# Main_Board_v6.net
KiCad netlist of a schematic drawn in EAGLE
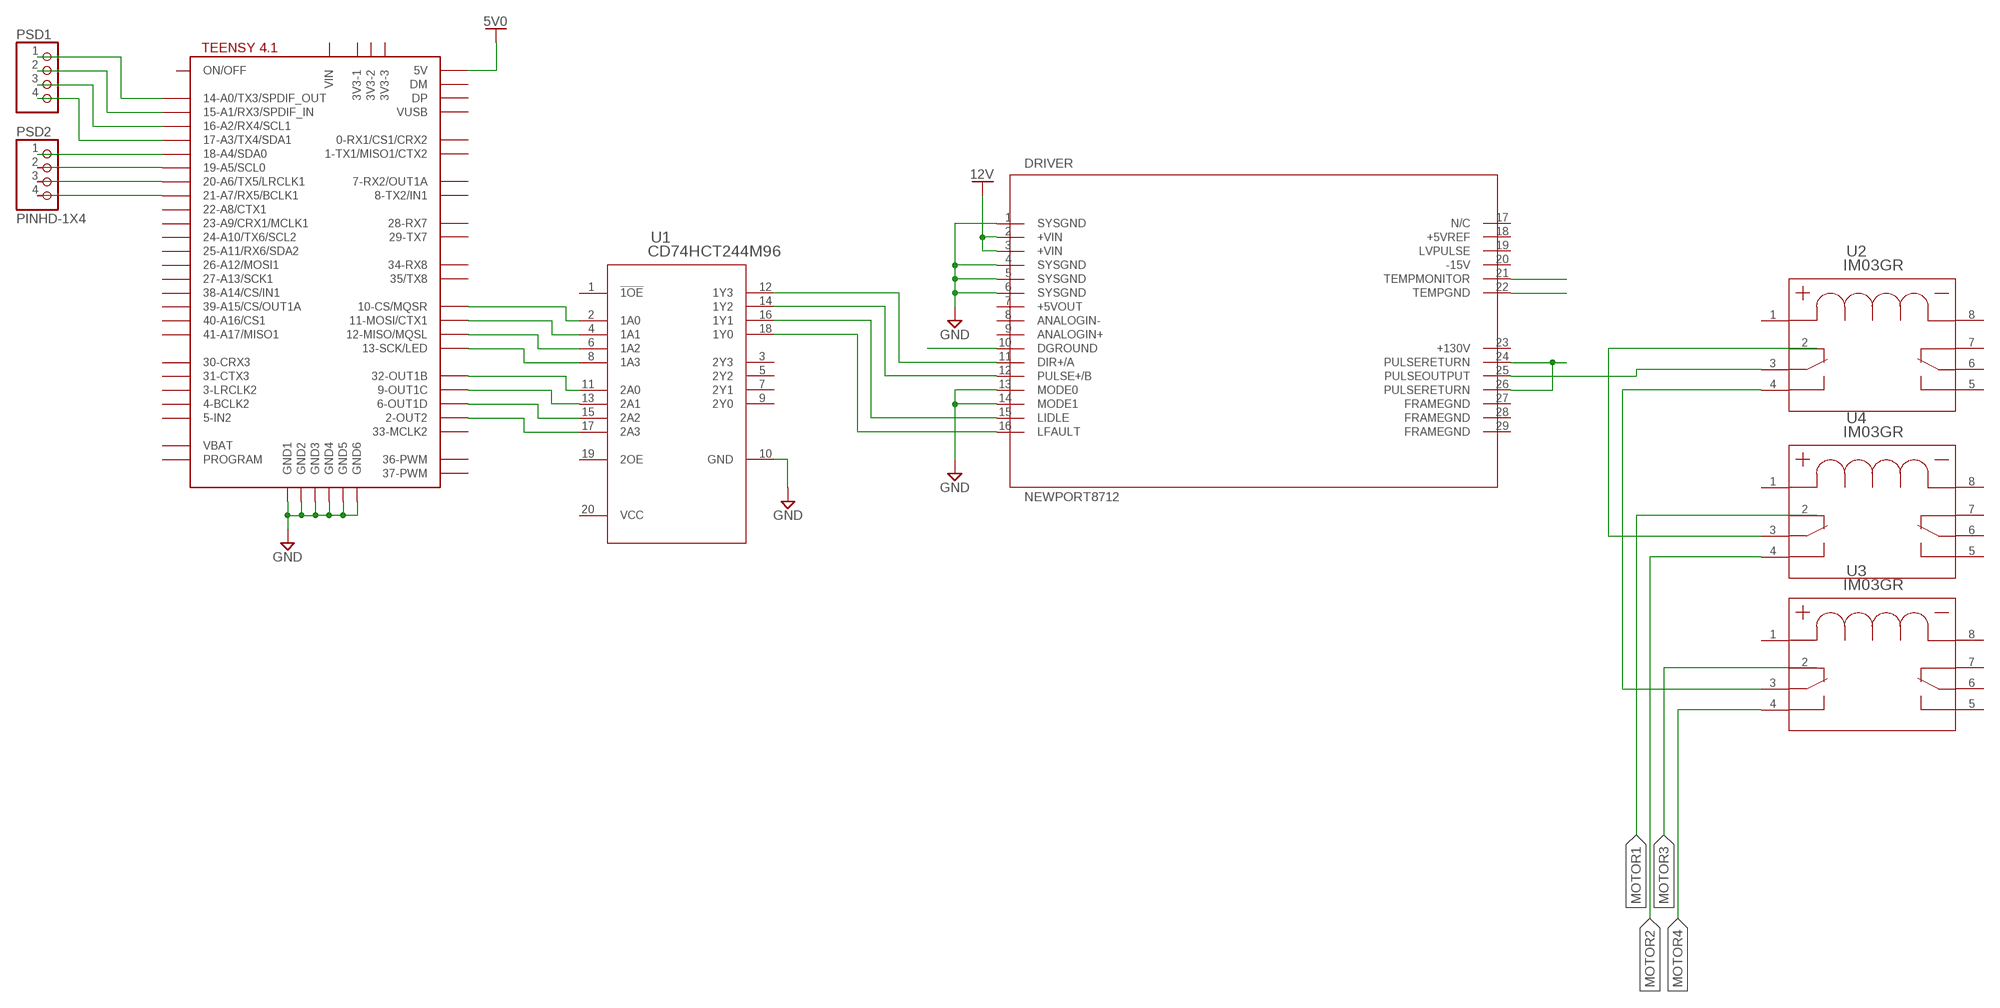
[diagram p0: schematic, sheet 1]

(export (version "E")
  (design (tool "Eeschema 10.0.6"))
  (components
    (comp (ref "DRIVER")
      (value "NEWPORT8712")
      (footprint "eagle-import:NEWPORT8712")
      (libsource (lib "eagle-import") (part "NEWPORT8712"))
    )
    (comp (ref "PSD1")
      (value "PINHD-1X4")
      (footprint "eagle-import:1X04")
      (libsource (lib "eagle-import") (part "PINHD-1X4"))
    )
    (comp (ref "PSD2")
      (value "PINHD-1X4")
      (footprint "eagle-import:1X04")
      (libsource (lib "eagle-import") (part "PINHD-1X4"))
    )
    (comp (ref "U$2")
      (value "TEENSY41-E")
      (footprint "eagle-import:TENNSY41-E")
      (libsource (lib "eagle-import") (part "TEENSY41-E"))
    )
    (comp (ref "U1")
      (value "CD74HCT244M96")
      (footprint "eagle-import:DW20")
      (fields
        (field (name "GENERIC_PART_NUMBER") "CD74HCT244")
        (field (name "MANUFACTURER") "Texas Instruments")
      )
      (libsource (lib "eagle-import") (part "CD74HCT244M96"))
    )
    (comp (ref "U2")
      (value "IM03GR")
      (footprint "eagle-import:RELAY8-239X396_230")
      (fields (field (name "COPYRIGHT") "Copyright (C) 2016 Accelerated Designs. All rights reserved"))
      (libsource (lib "eagle-import") (part "IM03GR"))
    )
    (comp (ref "U3")
      (value "IM03GR")
      (footprint "eagle-import:RELAY8-239X396_230")
      (fields (field (name "COPYRIGHT") "Copyright (C) 2016 Accelerated Designs. All rights reserved"))
      (libsource (lib "eagle-import") (part "IM03GR"))
    )
    (comp (ref "U4")
      (value "IM03GR")
      (footprint "eagle-import:RELAY8-239X396_230")
      (fields (field (name "COPYRIGHT") "Copyright (C) 2016 Accelerated Designs. All rights reserved"))
      (libsource (lib "eagle-import") (part "IM03GR"))
    )
  )
  (nets
    (net (code "1") (name "/VCC") (class "Default")
      (node (ref "U1") (pin "20") (pinfunction "VCC_20") (pintype "power_in"))
    )
    (net (code "2") (name "5V0") (class "Default")
      (node (ref "U$2") (pin "+5V") (pinfunction "5V_+5V") (pintype "bidirectional"))
    )
    (net (code "3") (name "12V") (class "Default")
      (node (ref "DRIVER") (pin "2") (pinfunction "+VIN_2") (pintype "bidirectional"))
      (node (ref "DRIVER") (pin "3") (pinfunction "+VIN_3") (pintype "bidirectional"))
    )
    (net (code "4") (name "GND") (class "Default")
      (node (ref "DRIVER") (pin "1") (pinfunction "SYSGND_1") (pintype "bidirectional"))
      (node (ref "DRIVER") (pin "13") (pinfunction "MODE0_13") (pintype "bidirectional"))
      (node (ref "DRIVER") (pin "14") (pinfunction "MODE1_14") (pintype "bidirectional"))
      (node (ref "DRIVER") (pin "4") (pinfunction "SYSGND_4") (pintype "bidirectional"))
      (node (ref "DRIVER") (pin "5") (pinfunction "SYSGND_5") (pintype "bidirectional"))
      (node (ref "DRIVER") (pin "6") (pinfunction "SYSGND_6") (pintype "bidirectional"))
      (node (ref "U$2") (pin "GND1") (pinfunction "GND1_GND1") (pintype "bidirectional"))
      (node (ref "U$2") (pin "GND2") (pinfunction "GND2_GND2") (pintype "bidirectional"))
      (node (ref "U$2") (pin "GND3") (pinfunction "GND3_GND3") (pintype "bidirectional"))
      (node (ref "U$2") (pin "GND4") (pinfunction "GND4_GND4") (pintype "bidirectional"))
      (node (ref "U$2") (pin "GND5") (pinfunction "GND5_GND5") (pintype "bidirectional"))
      (node (ref "U$2") (pin "GND6") (pinfunction "GND6_GND6") (pintype "bidirectional"))
      (node (ref "U1") (pin "10") (pinfunction "GND_10") (pintype "power_in"))
    )
    (net (code "5") (name "MOTOR1") (class "Default")
      (node (ref "U4") (pin "2") (pinfunction "2_2") (pintype "passive"))
    )
    (net (code "6") (name "MOTOR2") (class "Default")
      (node (ref "U4") (pin "4") (pinfunction "4_4") (pintype "passive"))
    )
    (net (code "7") (name "MOTOR3") (class "Default")
      (node (ref "U3") (pin "2") (pinfunction "2_2") (pintype "passive"))
    )
    (net (code "8") (name "MOTOR4") (class "Default")
      (node (ref "U3") (pin "4") (pinfunction "4_4") (pintype "passive"))
    )
    (net (code "9") (name "Net-(DRIVER-DIR+{slash}A)") (class "Default")
      (node (ref "DRIVER") (pin "11") (pinfunction "DIR+/A_11") (pintype "bidirectional"))
      (node (ref "U1") (pin "12") (pinfunction "1Y3_12") (pintype "output"))
    )
    (net (code "10") (name "Net-(DRIVER-LFAULT)") (class "Default")
      (node (ref "DRIVER") (pin "16") (pinfunction "LFAULT_16") (pintype "bidirectional"))
      (node (ref "U1") (pin "18") (pinfunction "1Y0_18") (pintype "output"))
    )
    (net (code "11") (name "Net-(DRIVER-LIDLE)") (class "Default")
      (node (ref "DRIVER") (pin "15") (pinfunction "LIDLE_15") (pintype "bidirectional"))
      (node (ref "U1") (pin "16") (pinfunction "1Y1_16") (pintype "output"))
    )
    (net (code "12") (name "Net-(DRIVER-PULSE+{slash}B)") (class "Default")
      (node (ref "DRIVER") (pin "12") (pinfunction "PULSE+/B_12") (pintype "bidirectional"))
      (node (ref "U1") (pin "14") (pinfunction "1Y2_14") (pintype "output"))
    )
    (net (code "13") (name "Net-(DRIVER-PULSEOUTPUT)") (class "Default")
      (node (ref "DRIVER") (pin "25") (pinfunction "PULSEOUTPUT_25") (pintype "bidirectional"))
      (node (ref "U2") (pin "3") (pinfunction "3_3") (pintype "passive"))
    )
    (net (code "14") (name "Net-(DRIVER-PULSERETURN-Pad24)") (class "Default")
      (node (ref "DRIVER") (pin "24") (pinfunction "PULSERETURN_24") (pintype "bidirectional"))
      (node (ref "DRIVER") (pin "26") (pinfunction "PULSERETURN_26") (pintype "bidirectional"))
    )
    (net (code "15") (name "Net-(PSD1-Pad1)") (class "Default")
      (node (ref "PSD1") (pin "1") (pinfunction "1_1") (pintype "passive"))
      (node (ref "U$2") (pin "14-A0/TX3/SPDIF_OUT") (pinfunction "14-A0/TX3/SPDIF_OUT_14-A0/TX3/SPDIF_OUT") (pintype "bidirectional"))
    )
    (net (code "16") (name "Net-(PSD1-Pad2)") (class "Default")
      (node (ref "PSD1") (pin "2") (pinfunction "2_2") (pintype "passive"))
      (node (ref "U$2") (pin "15-A1/RX3/SPDIF_IN") (pinfunction "15-A1/RX3/SPDIF_IN_15-A1/RX3/SPDIF_IN") (pintype "bidirectional"))
    )
    (net (code "17") (name "Net-(PSD1-Pad3)") (class "Default")
      (node (ref "PSD1") (pin "3") (pinfunction "3_3") (pintype "passive"))
      (node (ref "U$2") (pin "16-A2/RX4/SCL1") (pinfunction "16-A2/RX4/SCL1_16-A2/RX4/SCL1") (pintype "bidirectional"))
    )
    (net (code "18") (name "Net-(PSD1-Pad4)") (class "Default")
      (node (ref "PSD1") (pin "4") (pinfunction "4_4") (pintype "passive"))
      (node (ref "U$2") (pin "17-A3/TX4/SDA1") (pinfunction "17-A3/TX4/SDA1_17-A3/TX4/SDA1") (pintype "bidirectional"))
    )
    (net (code "19") (name "Net-(PSD2-Pad1)") (class "Default")
      (node (ref "PSD2") (pin "1") (pinfunction "1_1") (pintype "passive"))
      (node (ref "U$2") (pin "18-A4/SDA0") (pinfunction "18-A4/SDA0_18-A4/SDA0") (pintype "bidirectional"))
    )
    (net (code "20") (name "Net-(PSD2-Pad2)") (class "Default")
      (node (ref "PSD2") (pin "2") (pinfunction "2_2") (pintype "passive"))
      (node (ref "U$2") (pin "19-A5/SCL0") (pinfunction "19-A5/SCL0_19-A5/SCL0") (pintype "bidirectional"))
    )
    (net (code "21") (name "Net-(PSD2-Pad3)") (class "Default")
      (node (ref "PSD2") (pin "3") (pinfunction "3_3") (pintype "passive"))
      (node (ref "U$2") (pin "20-A6/TX5/LRCLK1") (pinfunction "20-A6/TX5/LRCLK1_20-A6/TX5/LRCLK1") (pintype "bidirectional"))
    )
    (net (code "22") (name "Net-(PSD2-Pad4)") (class "Default")
      (node (ref "PSD2") (pin "4") (pinfunction "4_4") (pintype "passive"))
      (node (ref "U$2") (pin "21-A7/RX5/BCLK1") (pinfunction "21-A7/RX5/BCLK1_21-A7/RX5/BCLK1") (pintype "bidirectional"))
    )
    (net (code "23") (name "Net-(U$2-10-CS{slash}MQSR)") (class "Default")
      (node (ref "U$2") (pin "10-CS\\MQSR") (pinfunction "10-CS/MQSR_10-CS\\MQSR") (pintype "bidirectional"))
      (node (ref "U1") (pin "2") (pinfunction "1A0_2") (pintype "input"))
    )
    (net (code "24") (name "Net-(U1-1A1)") (class "Default")
      (node (ref "U$2") (pin "11-MOSI/CTX1") (pinfunction "11-MOSI/CTX1_11-MOSI/CTX1") (pintype "bidirectional"))
      (node (ref "U1") (pin "4") (pinfunction "1A1_4") (pintype "input"))
    )
    (net (code "25") (name "Net-(U1-1A2)") (class "Default")
      (node (ref "U$2") (pin "12-MISO/MQSL") (pinfunction "12-MISO/MQSL_12-MISO/MQSL") (pintype "bidirectional"))
      (node (ref "U1") (pin "6") (pinfunction "1A2_6") (pintype "input"))
    )
    (net (code "26") (name "Net-(U1-1A3)") (class "Default")
      (node (ref "U$2") (pin "13-SCK/LED") (pinfunction "13-SCK/LED_13-SCK/LED") (pintype "bidirectional"))
      (node (ref "U1") (pin "8") (pinfunction "1A3_8") (pintype "input"))
    )
    (net (code "27") (name "Net-(U1-2A0)") (class "Default")
      (node (ref "U$2") (pin "32-OUT1B") (pinfunction "32-OUT1B_32-OUT1B") (pintype "bidirectional"))
      (node (ref "U1") (pin "11") (pinfunction "2A0_11") (pintype "input"))
    )
    (net (code "28") (name "Net-(U1-2A1)") (class "Default")
      (node (ref "U$2") (pin "9-OUT1C") (pinfunction "9-OUT1C_9-OUT1C") (pintype "bidirectional"))
      (node (ref "U1") (pin "13") (pinfunction "2A1_13") (pintype "input"))
    )
    (net (code "29") (name "Net-(U1-2A2)") (class "Default")
      (node (ref "U$2") (pin "6-OUT1D") (pinfunction "6-OUT1D_6-OUT1D") (pintype "bidirectional"))
      (node (ref "U1") (pin "15") (pinfunction "2A2_15") (pintype "input"))
    )
    (net (code "30") (name "Net-(U1-2A3)") (class "Default")
      (node (ref "U$2") (pin "2-OUT2") (pinfunction "2-OUT2_2-OUT2") (pintype "bidirectional"))
      (node (ref "U1") (pin "17") (pinfunction "2A3_17") (pintype "input"))
    )
    (net (code "31") (name "Net-(U2-Pad2)") (class "Default")
      (node (ref "U2") (pin "2") (pinfunction "2_2") (pintype "passive"))
      (node (ref "U4") (pin "3") (pinfunction "3_3") (pintype "passive"))
    )
    (net (code "32") (name "Net-(U2-Pad4)") (class "Default")
      (node (ref "U2") (pin "4") (pinfunction "4_4") (pintype "passive"))
      (node (ref "U3") (pin "3") (pinfunction "3_3") (pintype "passive"))
    )
    (net (code "33") (name "unconnected-(DRIVER-+5VOUT-Pad7)") (class "Default")
      (node (ref "DRIVER") (pin "7") (pinfunction "+5VOUT_7") (pintype "bidirectional"))
    )
    (net (code "34") (name "unconnected-(DRIVER-+5VREF-Pad18)") (class "Default")
      (node (ref "DRIVER") (pin "18") (pinfunction "+5VREF_18") (pintype "bidirectional"))
    )
    (net (code "35") (name "unconnected-(DRIVER-+130V-Pad23)") (class "Default")
      (node (ref "DRIVER") (pin "23") (pinfunction "+130V_23") (pintype "bidirectional"))
    )
    (net (code "36") (name "unconnected-(DRIVER--15V-Pad20)") (class "Default")
      (node (ref "DRIVER") (pin "20") (pinfunction "-15V_20") (pintype "bidirectional"))
    )
    (net (code "37") (name "unconnected-(DRIVER-ANALOGIN+-Pad9)") (class "Default")
      (node (ref "DRIVER") (pin "9") (pinfunction "ANALOGIN+_9") (pintype "bidirectional"))
    )
    (net (code "38") (name "unconnected-(DRIVER-ANALOGIN--Pad8)") (class "Default")
      (node (ref "DRIVER") (pin "8") (pinfunction "ANALOGIN-_8") (pintype "bidirectional"))
    )
    (net (code "39") (name "unconnected-(DRIVER-DGROUND-Pad10)") (class "Default")
      (node (ref "DRIVER") (pin "10") (pinfunction "DGROUND_10") (pintype "bidirectional"))
    )
    (net (code "40") (name "unconnected-(DRIVER-FRAMEGND-Pad27)") (class "Default")
      (node (ref "DRIVER") (pin "27") (pinfunction "FRAMEGND_27") (pintype "bidirectional"))
    )
    (net (code "41") (name "unconnected-(DRIVER-FRAMEGND-Pad28)") (class "Default")
      (node (ref "DRIVER") (pin "28") (pinfunction "FRAMEGND_28") (pintype "bidirectional"))
    )
    (net (code "42") (name "unconnected-(DRIVER-FRAMEGND-Pad29)") (class "Default")
      (node (ref "DRIVER") (pin "29") (pinfunction "FRAMEGND_29") (pintype "bidirectional"))
    )
    (net (code "43") (name "unconnected-(DRIVER-LVPULSE-Pad19)") (class "Default")
      (node (ref "DRIVER") (pin "19") (pinfunction "LVPULSE_19") (pintype "bidirectional"))
    )
    (net (code "44") (name "unconnected-(DRIVER-N{slash}C-Pad17)") (class "Default")
      (node (ref "DRIVER") (pin "17") (pinfunction "N/C_17") (pintype "bidirectional"))
    )
    (net (code "45") (name "unconnected-(DRIVER-TEMPGND-Pad22)") (class "Default")
      (node (ref "DRIVER") (pin "22") (pinfunction "TEMPGND_22") (pintype "bidirectional"))
    )
    (net (code "46") (name "unconnected-(DRIVER-TEMPMONITOR-Pad21)") (class "Default")
      (node (ref "DRIVER") (pin "21") (pinfunction "TEMPMONITOR_21") (pintype "bidirectional"))
    )
    (net (code "47") (name "unconnected-(U$2-35{slash}TX8-Pad35-TX8)") (class "Default")
      (node (ref "U$2") (pin "35-TX8") (pinfunction "35/TX8_35-TX8") (pintype "bidirectional"))
    )
    (net (code "48") (name "unconnected-(U$2-Pad0-RX1{slash}CS1{slash}CRX2)") (class "Default")
      (node (ref "U$2") (pin "0-RX1/CS1/CRX2") (pinfunction "0-RX1/CS1/CRX2_0-RX1/CS1/CRX2") (pintype "bidirectional"))
    )
    (net (code "49") (name "unconnected-(U$2-Pad1-TX1{slash}MISO1{slash}CTX2)") (class "Default")
      (node (ref "U$2") (pin "1-TX1/MISO1/CTX2") (pinfunction "1-TX1/MISO1/CTX2_1-TX1/MISO1/CTX2") (pintype "bidirectional"))
    )
    (net (code "50") (name "unconnected-(U$2-Pad3-LRCLK2)") (class "Default")
      (node (ref "U$2") (pin "3-LRCLK2") (pinfunction "3-LRCLK2_3-LRCLK2") (pintype "bidirectional"))
    )
    (net (code "51") (name "unconnected-(U$2-Pad3V3-1)") (class "Default")
      (node (ref "U$2") (pin "3V3-1") (pinfunction "3V3-1_3V3-1") (pintype "bidirectional"))
    )
    (net (code "52") (name "unconnected-(U$2-Pad3V3-2)") (class "Default")
      (node (ref "U$2") (pin "3V3-2") (pinfunction "3V3-2_3V3-2") (pintype "bidirectional"))
    )
    (net (code "53") (name "unconnected-(U$2-Pad3V3-3)") (class "Default")
      (node (ref "U$2") (pin "3V3-3") (pinfunction "3V3-3_3V3-3") (pintype "bidirectional"))
    )
    (net (code "54") (name "unconnected-(U$2-Pad4-BCLK2)") (class "Default")
      (node (ref "U$2") (pin "4-BCLK2") (pinfunction "4-BCLK2_4-BCLK2") (pintype "bidirectional"))
    )
    (net (code "55") (name "unconnected-(U$2-Pad5-IN2)") (class "Default")
      (node (ref "U$2") (pin "5-IN2") (pinfunction "5-IN2_5-IN2") (pintype "bidirectional"))
    )
    (net (code "56") (name "unconnected-(U$2-Pad7-RX2{slash}OUT1A)") (class "Default")
      (node (ref "U$2") (pin "7-RX2/OUT1A") (pinfunction "7-RX2/OUT1A_7-RX2/OUT1A") (pintype "bidirectional"))
    )
    (net (code "57") (name "unconnected-(U$2-Pad8-TX2{slash}IN1)") (class "Default")
      (node (ref "U$2") (pin "8-TX2/IN1") (pinfunction "8-TX2/IN1_8-TX2/IN1") (pintype "bidirectional"))
    )
    (net (code "58") (name "unconnected-(U$2-Pad22-A8{slash}CTX1)") (class "Default")
      (node (ref "U$2") (pin "22-A8/CTX1") (pinfunction "22-A8/CTX1_22-A8/CTX1") (pintype "bidirectional"))
    )
    (net (code "59") (name "unconnected-(U$2-Pad23-A9{slash}CRX1{slash}MCLK1)") (class "Default")
      (node (ref "U$2") (pin "23-A9/CRX1/MCLK1") (pinfunction "23-A9/CRX1/MCLK1_23-A9/CRX1/MCLK1") (pintype "bidirectional"))
    )
    (net (code "60") (name "unconnected-(U$2-Pad24-A10{slash}TX6{slash}SCL2)") (class "Default")
      (node (ref "U$2") (pin "24-A10/TX6/SCL2") (pinfunction "24-A10/TX6/SCL2_24-A10/TX6/SCL2") (pintype "bidirectional"))
    )
    (net (code "61") (name "unconnected-(U$2-Pad25-A11{slash}RX6{slash}SDA2)") (class "Default")
      (node (ref "U$2") (pin "25-A11/RX6/SDA2") (pinfunction "25-A11/RX6/SDA2_25-A11/RX6/SDA2") (pintype "bidirectional"))
    )
    (net (code "62") (name "unconnected-(U$2-Pad26-A12{slash}MOSI1)") (class "Default")
      (node (ref "U$2") (pin "26-A12/MOSI1") (pinfunction "26-A12/MOSI1_26-A12/MOSI1") (pintype "bidirectional"))
    )
    (net (code "63") (name "unconnected-(U$2-Pad27-A13{slash}SCK1)") (class "Default")
      (node (ref "U$2") (pin "27-A13/SCK1") (pinfunction "27-A13/SCK1_27-A13/SCK1") (pintype "bidirectional"))
    )
    (net (code "64") (name "unconnected-(U$2-Pad28-RX7)") (class "Default")
      (node (ref "U$2") (pin "28-RX7") (pinfunction "28-RX7_28-RX7") (pintype "bidirectional"))
    )
    (net (code "65") (name "unconnected-(U$2-Pad29-TX7)") (class "Default")
      (node (ref "U$2") (pin "29-TX7") (pinfunction "29-TX7_29-TX7") (pintype "bidirectional"))
    )
    (net (code "66") (name "unconnected-(U$2-Pad30-CRX3)") (class "Default")
      (node (ref "U$2") (pin "30-CRX3") (pinfunction "30-CRX3_30-CRX3") (pintype "bidirectional"))
    )
    (net (code "67") (name "unconnected-(U$2-Pad31-CTX3)") (class "Default")
      (node (ref "U$2") (pin "31-CTX3") (pinfunction "31-CTX3_31-CTX3") (pintype "bidirectional"))
    )
    (net (code "68") (name "unconnected-(U$2-Pad33-MCLK2)") (class "Default")
      (node (ref "U$2") (pin "33-MCLK2") (pinfunction "33-MCLK2_33-MCLK2") (pintype "bidirectional"))
    )
    (net (code "69") (name "unconnected-(U$2-Pad34-RX8)") (class "Default")
      (node (ref "U$2") (pin "34-RX8") (pinfunction "34-RX8_34-RX8") (pintype "bidirectional"))
    )
    (net (code "70") (name "unconnected-(U$2-Pad36-PWM)") (class "Default")
      (node (ref "U$2") (pin "36-PWM") (pinfunction "36-PWM_36-PWM") (pintype "bidirectional"))
    )
    (net (code "71") (name "unconnected-(U$2-Pad37-PWM)") (class "Default")
      (node (ref "U$2") (pin "37-PWM") (pinfunction "37-PWM_37-PWM") (pintype "bidirectional"))
    )
    (net (code "72") (name "unconnected-(U$2-Pad38-A14{slash}CS{slash}IN1)") (class "Default")
      (node (ref "U$2") (pin "38-A14/CS/IN1") (pinfunction "38-A14/CS/IN1_38-A14/CS/IN1") (pintype "bidirectional"))
    )
    (net (code "73") (name "unconnected-(U$2-Pad39-A15{slash}CS{slash}OUT1A)") (class "Default")
      (node (ref "U$2") (pin "39-A15/CS/OUT1A") (pinfunction "39-A15/CS/OUT1A_39-A15/CS/OUT1A") (pintype "bidirectional"))
    )
    (net (code "74") (name "unconnected-(U$2-Pad40-A16{slash}CS1)") (class "Default")
      (node (ref "U$2") (pin "40-A16/CS1") (pinfunction "40-A16/CS1_40-A16/CS1") (pintype "bidirectional"))
    )
    (net (code "75") (name "unconnected-(U$2-Pad41-A17{slash}MISO1)") (class "Default")
      (node (ref "U$2") (pin "41-A17/MISO1") (pinfunction "41-A17/MISO1_41-A17/MISO1") (pintype "bidirectional"))
    )
    (net (code "76") (name "unconnected-(U$2-PadDM)") (class "Default")
      (node (ref "U$2") (pin "DM") (pinfunction "DM_DM") (pintype "bidirectional"))
    )
    (net (code "77") (name "unconnected-(U$2-PadDP)") (class "Default")
      (node (ref "U$2") (pin "DP") (pinfunction "DP_DP") (pintype "bidirectional"))
    )
    (net (code "78") (name "unconnected-(U$2-PadON{slash}OFF)") (class "Default")
      (node (ref "U$2") (pin "ON/OFF") (pinfunction "ON/OFF_ON/OFF") (pintype "bidirectional"))
    )
    (net (code "79") (name "unconnected-(U$2-PadPROGRAM)") (class "Default")
      (node (ref "U$2") (pin "PROGRAM") (pinfunction "PROGRAM_PROGRAM") (pintype "bidirectional"))
    )
    (net (code "80") (name "unconnected-(U$2-PadVBAT)") (class "Default")
      (node (ref "U$2") (pin "VBAT") (pinfunction "VBAT_VBAT") (pintype "bidirectional"))
    )
    (net (code "81") (name "unconnected-(U$2-PadVIN)") (class "Default")
      (node (ref "U$2") (pin "VIN") (pinfunction "VIN_VIN") (pintype "bidirectional"))
    )
    (net (code "82") (name "unconnected-(U$2-PadVUSB)") (class "Default")
      (node (ref "U$2") (pin "VUSB") (pinfunction "VUSB_VUSB") (pintype "bidirectional"))
    )
    (net (code "83") (name "unconnected-(U1-2OE-Pad19)") (class "Default")
      (node (ref "U1") (pin "19") (pinfunction "2OE_19") (pintype "input"))
    )
    (net (code "84") (name "unconnected-(U1-2Y0-Pad9)") (class "Default")
      (node (ref "U1") (pin "9") (pinfunction "2Y0_9") (pintype "output"))
    )
    (net (code "85") (name "unconnected-(U1-2Y1-Pad7)") (class "Default")
      (node (ref "U1") (pin "7") (pinfunction "2Y1_7") (pintype "output"))
    )
    (net (code "86") (name "unconnected-(U1-2Y2-Pad5)") (class "Default")
      (node (ref "U1") (pin "5") (pinfunction "2Y2_5") (pintype "output"))
    )
    (net (code "87") (name "unconnected-(U1-2Y3-Pad3)") (class "Default")
      (node (ref "U1") (pin "3") (pinfunction "2Y3_3") (pintype "output"))
    )
    (net (code "88") (name "unconnected-(U1-~{1OE}-Pad1)") (class "Default")
      (node (ref "U1") (pin "1") (pinfunction "~{1OE}_1") (pintype "input"))
    )
    (net (code "89") (name "unconnected-(U2-Pad1)") (class "Default")
      (node (ref "U2") (pin "1") (pinfunction "1_1") (pintype "passive"))
    )
    (net (code "90") (name "unconnected-(U2-Pad5)") (class "Default")
      (node (ref "U2") (pin "5") (pinfunction "5_5") (pintype "passive"))
    )
    (net (code "91") (name "unconnected-(U2-Pad6)") (class "Default")
      (node (ref "U2") (pin "6") (pinfunction "6_6") (pintype "passive"))
    )
    (net (code "92") (name "unconnected-(U2-Pad7)") (class "Default")
      (node (ref "U2") (pin "7") (pinfunction "7_7") (pintype "passive"))
    )
    (net (code "93") (name "unconnected-(U2-Pad8)") (class "Default")
      (node (ref "U2") (pin "8") (pinfunction "8_8") (pintype "passive"))
    )
    (net (code "94") (name "unconnected-(U3-Pad1)") (class "Default")
      (node (ref "U3") (pin "1") (pinfunction "1_1") (pintype "passive"))
    )
    (net (code "95") (name "unconnected-(U3-Pad5)") (class "Default")
      (node (ref "U3") (pin "5") (pinfunction "5_5") (pintype "passive"))
    )
    (net (code "96") (name "unconnected-(U3-Pad6)") (class "Default")
      (node (ref "U3") (pin "6") (pinfunction "6_6") (pintype "passive"))
    )
    (net (code "97") (name "unconnected-(U3-Pad7)") (class "Default")
      (node (ref "U3") (pin "7") (pinfunction "7_7") (pintype "passive"))
    )
    (net (code "98") (name "unconnected-(U3-Pad8)") (class "Default")
      (node (ref "U3") (pin "8") (pinfunction "8_8") (pintype "passive"))
    )
    (net (code "99") (name "unconnected-(U4-Pad1)") (class "Default")
      (node (ref "U4") (pin "1") (pinfunction "1_1") (pintype "passive"))
    )
    (net (code "100") (name "unconnected-(U4-Pad5)") (class "Default")
      (node (ref "U4") (pin "5") (pinfunction "5_5") (pintype "passive"))
    )
    (net (code "101") (name "unconnected-(U4-Pad6)") (class "Default")
      (node (ref "U4") (pin "6") (pinfunction "6_6") (pintype "passive"))
    )
    (net (code "102") (name "unconnected-(U4-Pad7)") (class "Default")
      (node (ref "U4") (pin "7") (pinfunction "7_7") (pintype "passive"))
    )
    (net (code "103") (name "unconnected-(U4-Pad8)") (class "Default")
      (node (ref "U4") (pin "8") (pinfunction "8_8") (pintype "passive"))
    )
  )
)
